# 6_High_Voltage.net
KiCad netlist of a schematic drawn in Altium Designer
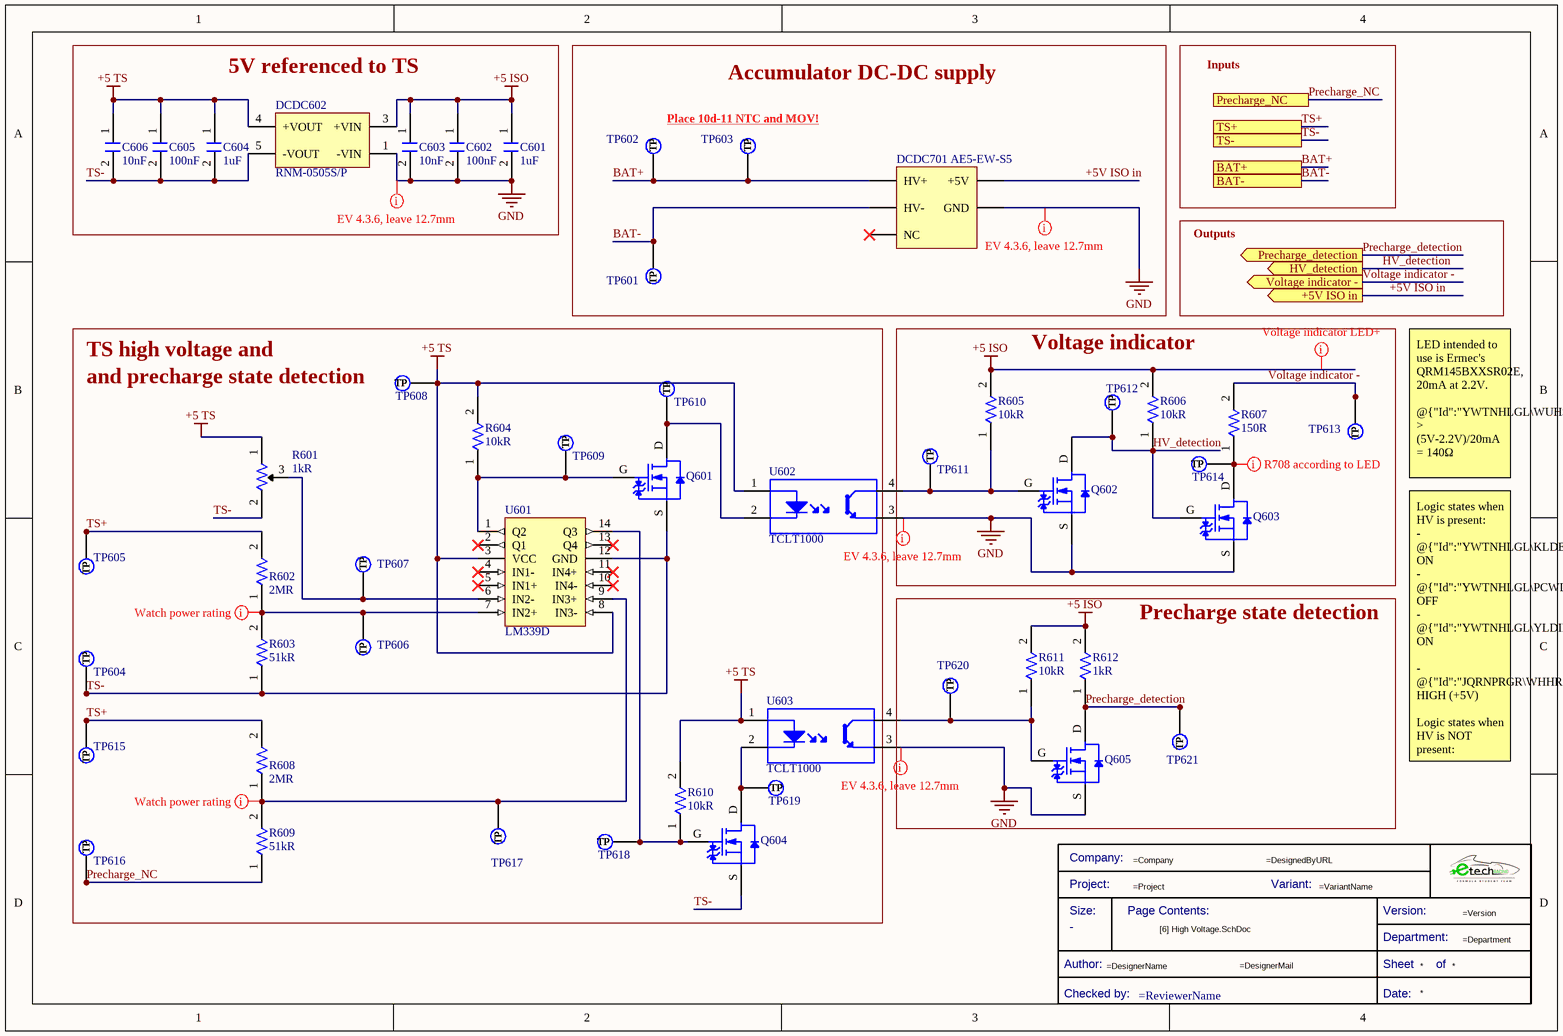
[diagram p0: [6] High Voltage.SchDoc]

(export (version "E")
  (design (tool "Eeschema 10.0.6"))
  (components
    (comp (ref "*")
      (value "Title Block_template")
      (description "Standard Title Block")
      (fields (field (name "SIZE") "-"))
      (libsource (lib "e-Tech_Racing") (part "Title Block_template"))
    )
    (comp (ref "C601")
      (value "885012207103")
      (footprint "C0805FNPC-R")
      (fields
        (field (name "TOLERANCE") "10%")
        (field (name "CAPACITANCE") "1uF")
        (field (name ".CREATOR") "GP")
      )
      (libsource (lib "Passives") (part "C1u-50V-0805FNPC-X7R"))
    )
    (comp (ref "C602")
      (value "885012207098")
      (footprint "C0805FNPC-R")
      (description "Cap, 0.1ΜF, 50V, 10%, X7R, 0805")
      (fields
        (field (name "TOLERANCE") "10%")
        (field (name "CAPACITANCE") "100nF")
        (field (name ".CREATOR") "DR")
      )
      (libsource (lib "Passives") (part "C100n-50V-0805FNPC-X7R"))
    )
    (comp (ref "C603")
      (value "885012207092")
      (footprint "C0805FNPC-R")
      (description "Cap, 0.01ΜF, 50V, 10%, X7R, 0805")
      (fields
        (field (name "TOLERANCE") "10%")
        (field (name "CAPACITANCE") "10nF")
        (field (name ".CREATOR") "DR")
      )
      (libsource (lib "Passives") (part "C10n-50V-0805FNPC-X7R"))
    )
    (comp (ref "C604")
      (value "885012207103")
      (footprint "C0805FNPC-R")
      (fields
        (field (name "TOLERANCE") "10%")
        (field (name "CAPACITANCE") "1uF")
        (field (name ".CREATOR") "GP")
      )
      (libsource (lib "Passives") (part "C1u-50V-0805FNPC-X7R"))
    )
    (comp (ref "C605")
      (value "885012207098")
      (footprint "C0805FNPC-R")
      (description "Cap, 0.1ΜF, 50V, 10%, X7R, 0805")
      (fields
        (field (name "TOLERANCE") "10%")
        (field (name "CAPACITANCE") "100nF")
        (field (name ".CREATOR") "DR")
      )
      (libsource (lib "Passives") (part "C100n-50V-0805FNPC-X7R"))
    )
    (comp (ref "C606")
      (value "885012207092")
      (footprint "C0805FNPC-R")
      (description "Cap, 0.01ΜF, 50V, 10%, X7R, 0805")
      (fields
        (field (name "TOLERANCE") "10%")
        (field (name "CAPACITANCE") "10nF")
        (field (name ".CREATOR") "DR")
      )
      (libsource (lib "Passives") (part "C10n-50V-0805FNPC-X7R"))
    )
    (comp (ref "DCDC602")
      (value "RNM-0505S/P")
      (footprint "DCDC_RNM-0505S/P")
      (description "1W DC/DC-Converter 'ECONOLINE' DIP6 1kV unreg; V. In: 05; V. Out: 05; mA. Out: 200")
      (fields
        (field (name "MANUFACTURER") "Recom")
        (field (name "MANUFACTURER PART NUMBER") "RNM-0505S/P")
        (field (name ".CREATOR") "GP")
      )
      (libsource (lib "Semiconductor") (part "DCDC_RNM-0505S/P"))
    )
    (comp (ref "DCDC701")
      (value "AE5-EW-S5")
      (footprint "DCDC_1000-5_ISO")
      (description "dc-dc isolated, 5 W, 100~1000 Vdc input, 5V, 1 A, DIP, ext temp")
      (fields (field (name "MANUFACTURER PART NUMBER 1") "AE5-EW-S5") (field (name ".CREATOR") "DR"))
      (libsource (lib "Semiconductor") (part "DCDC-ISO-1000V/5V-1A"))
    )
    (comp (ref "Q601")
      (value "CPH3455-TL-H")
      (footprint "TRT-NCH-3/35-CPH")
      (description "CPH3455-TL-H N-channel MOSFET Transistor; 3 A; 35 V; 3-Pin CPH")
      (fields (field (name "MANUFACTURER") "ON Semiconductor") (field (name ".CREATOR") "GP"))
      (libsource (lib "Semiconductor") (part "TRT-NCH-3/35-CPH"))
    )
    (comp (ref "Q602")
      (value "CPH3455-TL-H")
      (footprint "TRT-NCH-3/35-CPH")
      (description "CPH3455-TL-H N-channel MOSFET Transistor; 3 A; 35 V; 3-Pin CPH")
      (fields (field (name "MANUFACTURER") "ON Semiconductor") (field (name ".CREATOR") "GP"))
      (libsource (lib "Semiconductor") (part "TRT-NCH-3/35-CPH"))
    )
    (comp (ref "Q603")
      (value "CPH3455-TL-H")
      (footprint "TRT-NCH-3/35-CPH")
      (description "CPH3455-TL-H N-channel MOSFET Transistor; 3 A; 35 V; 3-Pin CPH")
      (fields (field (name "MANUFACTURER") "ON Semiconductor") (field (name ".CREATOR") "GP"))
      (libsource (lib "Semiconductor") (part "TRT-NCH-3/35-CPH"))
    )
    (comp (ref "Q604")
      (value "CPH3455-TL-H")
      (footprint "TRT-NCH-3/35-CPH")
      (description "CPH3455-TL-H N-channel MOSFET Transistor; 3 A; 35 V; 3-Pin CPH")
      (fields (field (name "MANUFACTURER") "ON Semiconductor") (field (name ".CREATOR") "GP"))
      (libsource (lib "Semiconductor") (part "TRT-NCH-3/35-CPH"))
    )
    (comp (ref "Q605")
      (value "CPH3455-TL-H")
      (footprint "TRT-NCH-3/35-CPH")
      (description "CPH3455-TL-H N-channel MOSFET Transistor; 3 A; 35 V; 3-Pin CPH")
      (fields (field (name "MANUFACTURER") "ON Semiconductor") (field (name ".CREATOR") "GP"))
      (libsource (lib "Semiconductor") (part "TRT-NCH-3/35-CPH"))
    )
    (comp (ref "R601")
      (value "3296Y-1-102LF")
      (footprint "R1k-VTR")
      (description "Res Cermet Trimmer 1K Ohm 10% 1/2W 25(Elec)Turn 2.19mm (9.53 X 4.83 X 11.55mm) Pin Thru-Hole Tube")
      (fields
        (field (name "MANUFACTURER") "Bourns")
        (field (name "TOLERANCE") "10%")
        (field (name "RESISTANCE") "1kR")
        (field (name ".CREATOR") "DO")
      )
      (libsource (lib "Passives") (part "R1k-VTR"))
    )
    (comp (ref "R602")
      (value "HVC1206-2M0FT3")
      (footprint "R1206FTK-W")
      (description "Res Thick Film 1206 2M Ohm 1% 0.3W ±100ppm/C Pad SMD T/R")
      (fields
        (field (name "MANUFACTURER") "TT Welwyn")
        (field (name "TOLERANCE") "1%")
        (field (name "RESISTENCE") "2MR")
        (field (name ".CREATOR") "DO")
      )
      (libsource (lib "Passives") (part "R2M-1206FTK"))
    )
    (comp (ref "R603")
      (value "CRCW120610K0FKEA")
      (footprint "R1206FTK-W")
      (description "Res Thick Film 1206 51K Ohm 1% 1/4W ±100ppm/°C Molded SMD SMD Punched Carrier T/R")
      (fields
        (field (name "MANUFACTURER") "Panasonic")
        (field (name "MANUFACTURER PART NUMBER") "ERJ-S08F5102V")
        (field (name "RESISTANCE") "51kR")
        (field (name ".CREATOR") "DO")
      )
      (libsource (lib "Passives") (part "R51k-1206FTK"))
    )
    (comp (ref "R604")
      (value "CR0805-JW-103ELF")
      (footprint "R0805FTK")
      (fields
        (field (name "TOLERANCE") "5%")
        (field (name "RESISTANCE") "10kR")
        (field (name ".CREATOR") "DR")
      )
      (libsource (lib "Passives") (part "R10k-0805FTK"))
    )
    (comp (ref "R605")
      (value "CR0805-JW-103ELF")
      (footprint "R0805FTK")
      (fields
        (field (name "TOLERANCE") "5%")
        (field (name "RESISTANCE") "10kR")
        (field (name ".CREATOR") "DR")
      )
      (libsource (lib "Passives") (part "R10k-0805FTK"))
    )
    (comp (ref "R606")
      (value "CR0805-JW-103ELF")
      (footprint "R0805FTK")
      (fields
        (field (name "TOLERANCE") "5%")
        (field (name "RESISTANCE") "10kR")
        (field (name ".CREATOR") "DR")
      )
      (libsource (lib "Passives") (part "R10k-0805FTK"))
    )
    (comp (ref "R607")
      (value "CRG1206F150R")
      (footprint "R1206FTK-W")
      (description "Res Thick Film 1206 150 Ohm 1% 0.25W(1/4W) ±100ppm/C Pad SMD T/R")
      (fields
        (field (name "MANUFACTURER") "TE Connectivity")
        (field (name "TOLERANCE") "1%")
        (field (name "RESISTANCE") "150R")
        (field (name ".CREATOR") "GP")
      )
      (libsource (lib "Passives") (part "R150-1206FTK"))
    )
    (comp (ref "R608")
      (value "HVC1206-2M0FT3")
      (footprint "R1206FTK-W")
      (description "Res Thick Film 1206 2M Ohm 1% 0.3W ±100ppm/C Pad SMD T/R")
      (fields
        (field (name "MANUFACTURER") "TT Welwyn")
        (field (name "TOLERANCE") "1%")
        (field (name "RESISTENCE") "2MR")
        (field (name ".CREATOR") "DO")
      )
      (libsource (lib "Passives") (part "R2M-1206FTK"))
    )
    (comp (ref "R609")
      (value "CRCW120610K0FKEA")
      (footprint "R1206FTK-W")
      (description "Res Thick Film 1206 51K Ohm 1% 1/4W ±100ppm/°C Molded SMD SMD Punched Carrier T/R")
      (fields
        (field (name "MANUFACTURER") "Panasonic")
        (field (name "MANUFACTURER PART NUMBER") "ERJ-S08F5102V")
        (field (name "RESISTANCE") "51kR")
        (field (name ".CREATOR") "DO")
      )
      (libsource (lib "Passives") (part "R51k-1206FTK"))
    )
    (comp (ref "R610")
      (value "CR0805-JW-103ELF")
      (footprint "R0805FTK")
      (fields
        (field (name "TOLERANCE") "5%")
        (field (name "RESISTANCE") "10kR")
        (field (name ".CREATOR") "DR")
      )
      (libsource (lib "Passives") (part "R10k-0805FTK"))
    )
    (comp (ref "R611")
      (value "CR0805-JW-103ELF")
      (footprint "R0805FTK")
      (fields
        (field (name "TOLERANCE") "5%")
        (field (name "RESISTANCE") "10kR")
        (field (name ".CREATOR") "DR")
      )
      (libsource (lib "Passives") (part "R10k-0805FTK"))
    )
    (comp (ref "R612")
      (value "CR0805-JW-102ELF")
      (footprint "R0805FTK")
      (description "Res Thick Film 0805 1K Ohm 5% 1/8W ±200ppm/°C Molded SMD SMD Paper Tape on Plastic Reel")
      (fields
        (field (name "TOLERANCE") "5%")
        (field (name "RESISTANCE") "1kR")
        (field (name ".CREATOR") "GP")
      )
      (libsource (lib "Passives") (part "R1k-0805FTK"))
    )
    (comp (ref "TP601")
      (value "TestPoint")
      (footprint "TestPoint")
      (description "Test Point 1x1 mm")
      (fields (field (name ".CREATOR") "GP") (field (name ".PCBCHECK") "GP") (field (name ".SCHCHECK") "GP"))
      (libsource (lib "e-Tech_Racing") (part "TestPoint"))
    )
    (comp (ref "TP602")
      (value "TestPoint")
      (footprint "TestPoint")
      (description "Test Point 1x1 mm")
      (fields (field (name ".CREATOR") "GP") (field (name ".PCBCHECK") "GP") (field (name ".SCHCHECK") "GP"))
      (libsource (lib "e-Tech_Racing") (part "TestPoint"))
    )
    (comp (ref "TP603")
      (value "TestPoint")
      (footprint "TestPoint")
      (description "Test Point 1x1 mm")
      (fields (field (name ".CREATOR") "GP") (field (name ".PCBCHECK") "GP") (field (name ".SCHCHECK") "GP"))
      (libsource (lib "e-Tech_Racing") (part "TestPoint"))
    )
    (comp (ref "TP604")
      (value "TestPoint")
      (footprint "TestPoint")
      (description "Test Point 1x1 mm")
      (fields (field (name ".CREATOR") "GP") (field (name ".PCBCHECK") "GP") (field (name ".SCHCHECK") "GP"))
      (libsource (lib "e-Tech_Racing") (part "TestPoint"))
    )
    (comp (ref "TP605")
      (value "TestPoint")
      (footprint "TestPoint")
      (description "Test Point 1x1 mm")
      (fields (field (name ".CREATOR") "GP") (field (name ".PCBCHECK") "GP") (field (name ".SCHCHECK") "GP"))
      (libsource (lib "e-Tech_Racing") (part "TestPoint"))
    )
    (comp (ref "TP606")
      (value "TestPoint")
      (footprint "TestPoint")
      (description "Test Point 1x1 mm")
      (fields (field (name ".CREATOR") "GP") (field (name ".PCBCHECK") "GP") (field (name ".SCHCHECK") "GP"))
      (libsource (lib "e-Tech_Racing") (part "TestPoint"))
    )
    (comp (ref "TP607")
      (value "TestPoint")
      (footprint "TestPoint")
      (description "Test Point 1x1 mm")
      (fields (field (name ".CREATOR") "GP") (field (name ".PCBCHECK") "GP") (field (name ".SCHCHECK") "GP"))
      (libsource (lib "e-Tech_Racing") (part "TestPoint"))
    )
    (comp (ref "TP608")
      (value "TestPoint")
      (footprint "TestPoint")
      (description "Test Point 1x1 mm")
      (fields (field (name ".CREATOR") "GP") (field (name ".PCBCHECK") "GP") (field (name ".SCHCHECK") "GP"))
      (libsource (lib "e-Tech_Racing") (part "TestPoint"))
    )
    (comp (ref "TP609")
      (value "TestPoint")
      (footprint "TestPoint")
      (description "Test Point 1x1 mm")
      (fields (field (name ".CREATOR") "GP") (field (name ".PCBCHECK") "GP") (field (name ".SCHCHECK") "GP"))
      (libsource (lib "e-Tech_Racing") (part "TestPoint"))
    )
    (comp (ref "TP610")
      (value "TestPoint")
      (footprint "TestPoint")
      (description "Test Point 1x1 mm")
      (fields (field (name ".CREATOR") "GP") (field (name ".PCBCHECK") "GP") (field (name ".SCHCHECK") "GP"))
      (libsource (lib "e-Tech_Racing") (part "TestPoint"))
    )
    (comp (ref "TP611")
      (value "TestPoint")
      (footprint "TestPoint")
      (description "Test Point 1x1 mm")
      (fields (field (name ".CREATOR") "GP") (field (name ".PCBCHECK") "GP") (field (name ".SCHCHECK") "GP"))
      (libsource (lib "e-Tech_Racing") (part "TestPoint"))
    )
    (comp (ref "TP612")
      (value "TestPoint")
      (footprint "TestPoint")
      (description "Test Point 1x1 mm")
      (fields (field (name ".CREATOR") "GP") (field (name ".PCBCHECK") "GP") (field (name ".SCHCHECK") "GP"))
      (libsource (lib "e-Tech_Racing") (part "TestPoint"))
    )
    (comp (ref "TP613")
      (value "TestPoint")
      (footprint "TestPoint")
      (description "Test Point 1x1 mm")
      (fields (field (name ".CREATOR") "GP") (field (name ".PCBCHECK") "GP") (field (name ".SCHCHECK") "GP"))
      (libsource (lib "e-Tech_Racing") (part "TestPoint"))
    )
    (comp (ref "TP614")
      (value "TestPoint")
      (footprint "TestPoint")
      (description "Test Point 1x1 mm")
      (fields (field (name ".CREATOR") "GP") (field (name ".PCBCHECK") "GP") (field (name ".SCHCHECK") "GP"))
      (libsource (lib "e-Tech_Racing") (part "TestPoint"))
    )
    (comp (ref "TP615")
      (value "TestPoint")
      (footprint "TestPoint")
      (description "Test Point 1x1 mm")
      (fields (field (name ".CREATOR") "GP") (field (name ".PCBCHECK") "GP") (field (name ".SCHCHECK") "GP"))
      (libsource (lib "e-Tech_Racing") (part "TestPoint"))
    )
    (comp (ref "TP616")
      (value "TestPoint")
      (footprint "TestPoint")
      (description "Test Point 1x1 mm")
      (fields (field (name ".CREATOR") "GP") (field (name ".PCBCHECK") "GP") (field (name ".SCHCHECK") "GP"))
      (libsource (lib "e-Tech_Racing") (part "TestPoint"))
    )
    (comp (ref "TP617")
      (value "TestPoint")
      (footprint "TestPoint")
      (description "Test Point 1x1 mm")
      (fields (field (name ".CREATOR") "GP") (field (name ".PCBCHECK") "GP") (field (name ".SCHCHECK") "GP"))
      (libsource (lib "e-Tech_Racing") (part "TestPoint"))
    )
    (comp (ref "TP618")
      (value "TestPoint")
      (footprint "TestPoint")
      (description "Test Point 1x1 mm")
      (fields (field (name ".CREATOR") "GP") (field (name ".PCBCHECK") "GP") (field (name ".SCHCHECK") "GP"))
      (libsource (lib "e-Tech_Racing") (part "TestPoint"))
    )
    (comp (ref "TP619")
      (value "TestPoint")
      (footprint "TestPoint")
      (description "Test Point 1x1 mm")
      (fields (field (name ".CREATOR") "GP") (field (name ".PCBCHECK") "GP") (field (name ".SCHCHECK") "GP"))
      (libsource (lib "e-Tech_Racing") (part "TestPoint"))
    )
    (comp (ref "TP620")
      (value "TestPoint")
      (footprint "TestPoint")
      (description "Test Point 1x1 mm")
      (fields (field (name ".CREATOR") "GP") (field (name ".PCBCHECK") "GP") (field (name ".SCHCHECK") "GP"))
      (libsource (lib "e-Tech_Racing") (part "TestPoint"))
    )
    (comp (ref "TP621")
      (value "TestPoint")
      (footprint "TestPoint")
      (description "Test Point 1x1 mm")
      (fields (field (name ".CREATOR") "GP") (field (name ".PCBCHECK") "GP") (field (name ".SCHCHECK") "GP"))
      (libsource (lib "e-Tech_Racing") (part "TestPoint"))
    )
    (comp (ref "U601")
      (value "LM339D")
      (footprint "Array_4_Amp_LM339D")
      (description "Comparator Quad ±18V/36V 14-Pin SOIC Tube")
      (fields
        (field (name "MANUFACTURER") "Texas Instruments")
        (field (name "MANUFACTURER PART NUMBER") "LM339D")
        (field (name ".CREATOR") "DO")
      )
      (libsource (lib "Integrated circuits") (part "Array_4_Amp_LM339D"))
    )
    (comp (ref "U602")
      (value "Optocoupler_TCLT1000")
      (footprint "Optocoupler_TCLT1000")
      (description "Optocoupler DC-IN 1-CH Transistor DC-OUT 4-Pin SOP T/R")
      (fields
        (field (name "MANUFACTURER") "Vishay Semiconductors")
        (field (name "MANUFACTURER PART NUMBER") "TCLT1000")
        (field (name "SUPPLIER PART NUMBER 1") "TCLT1000")
      )
      (libsource (lib "Semiconductor") (part "Optocoupler_TCLT1000"))
    )
    (comp (ref "U603")
      (value "Optocoupler_TCLT1000")
      (footprint "Optocoupler_TCLT1000")
      (description "Optocoupler DC-IN 1-CH Transistor DC-OUT 4-Pin SOP T/R")
      (fields
        (field (name "MANUFACTURER") "Vishay Semiconductors")
        (field (name "MANUFACTURER PART NUMBER") "TCLT1000")
        (field (name "SUPPLIER PART NUMBER 1") "TCLT1000")
      )
      (libsource (lib "Semiconductor") (part "Optocoupler_TCLT1000"))
    )
  )
  (nets
    (net (code "1") (name "+5 ISO") (class "Default")
      (node (ref "C601") (pin "1") (pinfunction "1_1") (pintype "passive"))
      (node (ref "C602") (pin "1") (pinfunction "1_1") (pintype "passive"))
      (node (ref "C603") (pin "1") (pinfunction "1_1") (pintype "passive"))
      (node (ref "DCDC602") (pin "3") (pinfunction "+VIN_3") (pintype "passive"))
      (node (ref "R605") (pin "2") (pinfunction "2_2") (pintype "passive"))
      (node (ref "R606") (pin "2") (pinfunction "2_2") (pintype "passive"))
      (node (ref "R611") (pin "2") (pinfunction "2_2") (pintype "passive"))
      (node (ref "R612") (pin "2") (pinfunction "2_2") (pintype "passive"))
    )
    (net (code "2") (name "+5 TS") (class "Default")
      (node (ref "C604") (pin "1") (pinfunction "1_1") (pintype "passive"))
      (node (ref "C605") (pin "1") (pinfunction "1_1") (pintype "passive"))
      (node (ref "C606") (pin "1") (pinfunction "1_1") (pintype "passive"))
      (node (ref "DCDC602") (pin "4") (pinfunction "+VOUT_4") (pintype "passive"))
      (node (ref "R601") (pin "1") (pinfunction "2_1") (pintype "passive"))
      (node (ref "R604") (pin "2") (pinfunction "2_2") (pintype "passive"))
      (node (ref "R610") (pin "2") (pinfunction "2_2") (pintype "passive"))
      (node (ref "TP608") (pin "1") (pinfunction "TP_1") (pintype "passive"))
      (node (ref "U601") (pin "3") (pinfunction "VCC_3") (pintype "power_in"))
      (node (ref "U601") (pin "8") (pinfunction "IN3-_8") (pintype "input"))
      (node (ref "U602") (pin "1") (pinfunction "A_1") (pintype "passive"))
      (node (ref "U603") (pin "1") (pinfunction "A_1") (pintype "passive"))
    )
    (net (code "3") (name "/+5V ISO in") (class "Default")
      (node (ref "DCDC701") (pin "4") (pinfunction "+5V_4") (pintype "passive"))
    )
    (net (code "4") (name "/BAT+") (class "Default")
      (node (ref "DCDC701") (pin "3") (pinfunction "HV+_3") (pintype "passive"))
      (node (ref "TP602") (pin "1") (pinfunction "TP_1") (pintype "passive"))
      (node (ref "TP603") (pin "1") (pinfunction "TP_1") (pintype "passive"))
    )
    (net (code "5") (name "/BAT-") (class "Default")
      (node (ref "DCDC701") (pin "2") (pinfunction "HV-_2") (pintype "passive"))
      (node (ref "TP601") (pin "1") (pinfunction "TP_1") (pintype "passive"))
    )
    (net (code "6") (name "/HV_detection") (class "Default")
      (node (ref "Q602") (pin "D") (pinfunction "D_D") (pintype "passive"))
      (node (ref "Q603") (pin "G") (pinfunction "G_G") (pintype "passive"))
      (node (ref "R606") (pin "1") (pinfunction "1_1") (pintype "passive"))
      (node (ref "TP612") (pin "1") (pinfunction "TP_1") (pintype "passive"))
    )
    (net (code "7") (name "/Precharge_NC") (class "Default")
      (node (ref "R609") (pin "1") (pinfunction "1_1") (pintype "passive"))
      (node (ref "TP616") (pin "1") (pinfunction "TP_1") (pintype "passive"))
    )
    (net (code "8") (name "/Precharge_detection") (class "Default")
      (node (ref "Q605") (pin "D") (pinfunction "D_D") (pintype "passive"))
      (node (ref "R612") (pin "1") (pinfunction "1_1") (pintype "passive"))
      (node (ref "TP621") (pin "1") (pinfunction "TP_1") (pintype "passive"))
    )
    (net (code "9") (name "/TS+") (class "Default")
      (node (ref "R602") (pin "2") (pinfunction "2_2") (pintype "passive"))
      (node (ref "R608") (pin "2") (pinfunction "2_2") (pintype "passive"))
      (node (ref "TP605") (pin "1") (pinfunction "TP_1") (pintype "passive"))
      (node (ref "TP615") (pin "1") (pinfunction "TP_1") (pintype "passive"))
    )
    (net (code "10") (name "/TS-") (class "Default")
      (node (ref "C604") (pin "2") (pinfunction "2_2") (pintype "passive"))
      (node (ref "C605") (pin "2") (pinfunction "2_2") (pintype "passive"))
      (node (ref "C606") (pin "2") (pinfunction "2_2") (pintype "passive"))
      (node (ref "DCDC602") (pin "5") (pinfunction "-VOUT_5") (pintype "passive"))
      (node (ref "Q601") (pin "S") (pinfunction "S_S") (pintype "passive"))
      (node (ref "Q604") (pin "S") (pinfunction "S_S") (pintype "passive"))
      (node (ref "R601") (pin "2") (pinfunction "2_2") (pintype "passive"))
      (node (ref "R603") (pin "1") (pinfunction "1_1") (pintype "passive"))
      (node (ref "TP604") (pin "1") (pinfunction "TP_1") (pintype "passive"))
      (node (ref "U601") (pin "12") (pinfunction "GND_12") (pintype "power_in"))
    )
    (net (code "11") (name "/Voltage indicator -") (class "Default")
      (node (ref "R607") (pin "2") (pinfunction "2_2") (pintype "passive"))
      (node (ref "TP613") (pin "1") (pinfunction "TP_1") (pintype "passive"))
    )
    (net (code "12") (name "GND") (class "Default")
      (node (ref "C601") (pin "2") (pinfunction "2_2") (pintype "passive"))
      (node (ref "C602") (pin "2") (pinfunction "2_2") (pintype "passive"))
      (node (ref "C603") (pin "2") (pinfunction "2_2") (pintype "passive"))
      (node (ref "DCDC602") (pin "1") (pinfunction "-VIN_1") (pintype "passive"))
      (node (ref "DCDC701") (pin "5") (pinfunction "GND_5") (pintype "passive"))
      (node (ref "Q602") (pin "S") (pinfunction "S_S") (pintype "passive"))
      (node (ref "Q603") (pin "S") (pinfunction "S_S") (pintype "passive"))
      (node (ref "Q605") (pin "S") (pinfunction "S_S") (pintype "passive"))
      (node (ref "U602") (pin "3") (pinfunction "C_3") (pintype "passive"))
      (node (ref "U603") (pin "3") (pinfunction "C_3") (pintype "passive"))
    )
    (net (code "13") (name "Net-(TP606-TP)") (class "Default")
      (node (ref "R602") (pin "1") (pinfunction "1_1") (pintype "passive"))
      (node (ref "R603") (pin "2") (pinfunction "2_2") (pintype "passive"))
      (node (ref "TP606") (pin "1") (pinfunction "TP_1") (pintype "passive"))
      (node (ref "U601") (pin "7") (pinfunction "IN2+_7") (pintype "input"))
    )
    (net (code "14") (name "Net-(TP607-TP)") (class "Default")
      (node (ref "R601") (pin "3") (pinfunction "3_3") (pintype "passive"))
      (node (ref "TP607") (pin "1") (pinfunction "TP_1") (pintype "passive"))
      (node (ref "U601") (pin "6") (pinfunction "IN2-_6") (pintype "input"))
    )
    (net (code "15") (name "Net-(TP609-TP)") (class "Default")
      (node (ref "Q601") (pin "G") (pinfunction "G_G") (pintype "passive"))
      (node (ref "R604") (pin "1") (pinfunction "1_1") (pintype "passive"))
      (node (ref "TP609") (pin "1") (pinfunction "TP_1") (pintype "passive"))
      (node (ref "U601") (pin "1") (pinfunction "Q2_1") (pintype "output"))
    )
    (net (code "16") (name "Net-(TP610-TP)") (class "Default")
      (node (ref "Q601") (pin "D") (pinfunction "D_D") (pintype "passive"))
      (node (ref "TP610") (pin "1") (pinfunction "TP_1") (pintype "passive"))
      (node (ref "U602") (pin "2") (pinfunction "K_2") (pintype "passive"))
    )
    (net (code "17") (name "Net-(TP611-TP)") (class "Default")
      (node (ref "Q602") (pin "G") (pinfunction "G_G") (pintype "passive"))
      (node (ref "R605") (pin "1") (pinfunction "1_1") (pintype "passive"))
      (node (ref "TP611") (pin "1") (pinfunction "TP_1") (pintype "passive"))
      (node (ref "U602") (pin "4") (pinfunction "E_4") (pintype "passive"))
    )
    (net (code "18") (name "Net-(TP614-TP)") (class "Default")
      (node (ref "Q603") (pin "D") (pinfunction "D_D") (pintype "passive"))
      (node (ref "R607") (pin "1") (pinfunction "1_1") (pintype "passive"))
      (node (ref "TP614") (pin "1") (pinfunction "TP_1") (pintype "passive"))
    )
    (net (code "19") (name "Net-(TP617-TP)") (class "Default")
      (node (ref "R608") (pin "1") (pinfunction "1_1") (pintype "passive"))
      (node (ref "R609") (pin "2") (pinfunction "2_2") (pintype "passive"))
      (node (ref "TP617") (pin "1") (pinfunction "TP_1") (pintype "passive"))
      (node (ref "U601") (pin "9") (pinfunction "IN3+_9") (pintype "input"))
    )
    (net (code "20") (name "Net-(TP618-TP)") (class "Default")
      (node (ref "Q604") (pin "G") (pinfunction "G_G") (pintype "passive"))
      (node (ref "R610") (pin "1") (pinfunction "1_1") (pintype "passive"))
      (node (ref "TP618") (pin "1") (pinfunction "TP_1") (pintype "passive"))
      (node (ref "U601") (pin "14") (pinfunction "Q3_14") (pintype "output"))
    )
    (net (code "21") (name "Net-(TP619-TP)") (class "Default")
      (node (ref "Q604") (pin "D") (pinfunction "D_D") (pintype "passive"))
      (node (ref "TP619") (pin "1") (pinfunction "TP_1") (pintype "passive"))
      (node (ref "U603") (pin "2") (pinfunction "K_2") (pintype "passive"))
    )
    (net (code "22") (name "Net-(TP620-TP)") (class "Default")
      (node (ref "Q605") (pin "G") (pinfunction "G_G") (pintype "passive"))
      (node (ref "R611") (pin "1") (pinfunction "1_1") (pintype "passive"))
      (node (ref "TP620") (pin "1") (pinfunction "TP_1") (pintype "passive"))
      (node (ref "U603") (pin "4") (pinfunction "E_4") (pintype "passive"))
    )
    (net (code "23") (name "unconnected-(DCDC701-NC-Pad1)") (class "Default")
      (node (ref "DCDC701") (pin "1") (pinfunction "NC_1") (pintype "passive+no_connect"))
    )
    (net (code "24") (name "unconnected-(U601-IN1+-Pad5)") (class "Default")
      (node (ref "U601") (pin "5") (pinfunction "IN1+_5") (pintype "input+no_connect"))
    )
    (net (code "25") (name "unconnected-(U601-IN1--Pad4)") (class "Default")
      (node (ref "U601") (pin "4") (pinfunction "IN1-_4") (pintype "input+no_connect"))
    )
    (net (code "26") (name "unconnected-(U601-IN4+-Pad11)") (class "Default")
      (node (ref "U601") (pin "11") (pinfunction "IN4+_11") (pintype "input+no_connect"))
    )
    (net (code "27") (name "unconnected-(U601-IN4--Pad10)") (class "Default")
      (node (ref "U601") (pin "10") (pinfunction "IN4-_10") (pintype "input+no_connect"))
    )
    (net (code "28") (name "unconnected-(U601-Q1-Pad2)") (class "Default")
      (node (ref "U601") (pin "2") (pinfunction "Q1_2") (pintype "output+no_connect"))
    )
    (net (code "29") (name "unconnected-(U601-Q4-Pad13)") (class "Default")
      (node (ref "U601") (pin "13") (pinfunction "Q4_13") (pintype "output+no_connect"))
    )
  )
)
